# ADC_AUX.net
KiCad netlist of a schematic drawn in Altium Designer
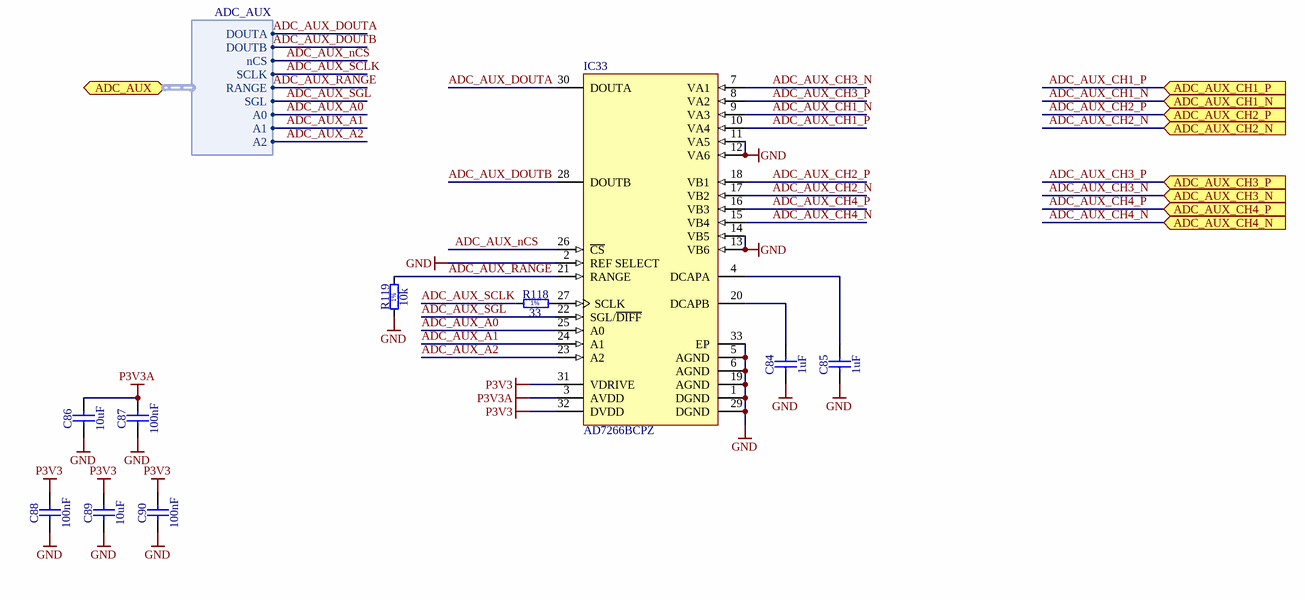
[diagram p0: ADC_AUX.SchDoc]

(export (version "E")
  (design (tool "Eeschema 10.0.6"))
  (components
    (comp (ref "C84")
      (value "1uF")
      (footprint "CAPC1005X55N")
      (description "Non-polarised capacitor")
      (fields
        (field (name "PART NUMBER") "CC0402_1UF_16V_10%_X5R")
        (field (name "VOLTAGE") "16V")
        (field (name "AUTHOR") "CERN DEM JLC")
      )
      (libsource (lib "Capacitors") (part "Capacitor - non polarized"))
    )
    (comp (ref "C85")
      (value "1uF")
      (footprint "CAPC1005X55N")
      (description "Non-polarised capacitor")
      (fields
        (field (name "PART NUMBER") "CC0402_1UF_16V_10%_X5R")
        (field (name "VOLTAGE") "16V")
        (field (name "AUTHOR") "CERN DEM JLC")
      )
      (libsource (lib "Capacitors") (part "Capacitor - non polarized"))
    )
    (comp (ref "C86")
      (value "10uF")
      (footprint "CAPC1608X80N")
      (description "Non-polarised capacitor")
      (fields
        (field (name "PART NUMBER") "CC0603_10UF_10V_10%_X5R")
        (field (name "VOLTAGE") "10V")
        (field (name "AUTHOR") "CERN DEM JLC")
      )
      (libsource (lib "Capacitors") (part "Capacitor - non polarized"))
    )
    (comp (ref "C87")
      (value "100nF")
      (footprint "CAPC1005X55N")
      (description "Non-polarised capacitor")
      (fields
        (field (name "PART NUMBER") "CC0402_100NF_16V_10%_X7R")
        (field (name "VOLTAGE") "16V")
        (field (name "AUTHOR") "CERN DEM JLC")
      )
      (libsource (lib "Capacitors") (part "Capacitor - non polarized"))
    )
    (comp (ref "C88")
      (value "100nF")
      (footprint "CAPC1005X55N")
      (description "Non-polarised capacitor")
      (fields
        (field (name "PART NUMBER") "CC0402_100NF_16V_10%_X7R")
        (field (name "VOLTAGE") "16V")
        (field (name "AUTHOR") "CERN DEM JLC")
      )
      (libsource (lib "Capacitors") (part "Capacitor - non polarized"))
    )
    (comp (ref "C89")
      (value "10uF")
      (footprint "CAPC1608X80N")
      (description "Non-polarised capacitor")
      (fields
        (field (name "PART NUMBER") "CC0603_10UF_10V_10%_X5R")
        (field (name "VOLTAGE") "10V")
        (field (name "AUTHOR") "CERN DEM JLC")
      )
      (libsource (lib "Capacitors") (part "Capacitor - non polarized"))
    )
    (comp (ref "C90")
      (value "100nF")
      (footprint "CAPC1005X55N")
      (description "Non-polarised capacitor")
      (fields
        (field (name "PART NUMBER") "CC0402_100NF_16V_10%_X7R")
        (field (name "VOLTAGE") "16V")
        (field (name "AUTHOR") "CERN DEM JLC")
      )
      (libsource (lib "Capacitors") (part "Capacitor - non polarized"))
    )
    (comp (ref "IC33")
      (value "AD7266BCPZ")
      (footprint "CP-32-2_N")
      (fields (field (name "MANUFACTURER") "Analog Devices") (field (name "GENERIC PART NUMBER") "AD7266"))
      (libsource (lib "Altium Content Vault") (part "ADI-AD7266-CP-32-2"))
    )
    (comp (ref "R118")
      (value "33")
      (footprint "RESC1005X40N")
      (description "Resistor - 1%")
      (fields
        (field (name "PART NUMBER") "R0402_33R_1%_0.0625W_100PPM")
        (field (name "MANUFACTURER") "GENERIC")
        (field (name "AUTHOR") "CERN DEM JLC")
      )
      (libsource (lib "Resistors") (part "Resistor - 1%"))
    )
    (comp (ref "R119")
      (value "10k")
      (footprint "RESC1005X40N")
      (description "Resistor - 1%")
      (fields
        (field (name "PART NUMBER") "R0402_10K_1%_0.0625W_100PPM")
        (field (name "MANUFACTURER") "GENERIC")
        (field (name "AUTHOR") "CERN DEM JLC")
      )
      (libsource (lib "Resistors") (part "Resistor - 1%"))
    )
  )
  (nets
    (net (code "2") (name "/ADC_AUX_A0") (class "Default")
      (node (ref "IC33") (pin "25") (pinfunction "A0_25") (pintype "input"))
    )
    (net (code "3") (name "/ADC_AUX_A1") (class "Default")
      (node (ref "IC33") (pin "24") (pinfunction "A1_24") (pintype "input"))
    )
    (net (code "4") (name "/ADC_AUX_A2") (class "Default")
      (node (ref "IC33") (pin "23") (pinfunction "A2_23") (pintype "input"))
    )
    (net (code "5") (name "/ADC_AUX_CH1_N") (class "Default")
      (node (ref "IC33") (pin "9") (pinfunction "VA3_9") (pintype "input"))
    )
    (net (code "6") (name "/ADC_AUX_CH1_P") (class "Default")
      (node (ref "IC33") (pin "10") (pinfunction "VA4_10") (pintype "input"))
    )
    (net (code "7") (name "/ADC_AUX_CH2_N") (class "Default")
      (node (ref "IC33") (pin "17") (pinfunction "VB2_17") (pintype "input"))
    )
    (net (code "8") (name "/ADC_AUX_CH2_P") (class "Default")
      (node (ref "IC33") (pin "18") (pinfunction "VB1_18") (pintype "input"))
    )
    (net (code "9") (name "/ADC_AUX_CH3_N") (class "Default")
      (node (ref "IC33") (pin "7") (pinfunction "VA1_7") (pintype "input"))
    )
    (net (code "10") (name "/ADC_AUX_CH3_P") (class "Default")
      (node (ref "IC33") (pin "8") (pinfunction "VA2_8") (pintype "input"))
    )
    (net (code "11") (name "/ADC_AUX_CH4_N") (class "Default")
      (node (ref "IC33") (pin "15") (pinfunction "VB4_15") (pintype "input"))
    )
    (net (code "12") (name "/ADC_AUX_CH4_P") (class "Default")
      (node (ref "IC33") (pin "16") (pinfunction "VB3_16") (pintype "input"))
    )
    (net (code "13") (name "/ADC_AUX_DOUTA") (class "Default")
      (node (ref "IC33") (pin "30") (pinfunction "DOUTA_30") (pintype "tri_state"))
    )
    (net (code "14") (name "/ADC_AUX_DOUTB") (class "Default")
      (node (ref "IC33") (pin "28") (pinfunction "DOUTB_28") (pintype "tri_state"))
    )
    (net (code "15") (name "/ADC_AUX_RANGE") (class "Default")
      (node (ref "IC33") (pin "21") (pinfunction "RANGE_21") (pintype "input"))
      (node (ref "R119") (pin "2") (pinfunction "2_2") (pintype "passive"))
    )
    (net (code "16") (name "/ADC_AUX_SCLK") (class "Default")
      (node (ref "R118") (pin "1") (pinfunction "1_1") (pintype "passive"))
    )
    (net (code "17") (name "/ADC_AUX_SGL") (class "Default")
      (node (ref "IC33") (pin "22") (pinfunction "SGL/~{DIFF}_22") (pintype "input"))
    )
    (net (code "18") (name "/ADC_AUX_nCS") (class "Default")
      (node (ref "IC33") (pin "26") (pinfunction "~{CS}_26") (pintype "input"))
    )
    (net (code "20") (name "GND") (class "Default")
      (node (ref "C84") (pin "1") (pinfunction "1_1") (pintype "passive"))
      (node (ref "C85") (pin "1") (pinfunction "1_1") (pintype "passive"))
      (node (ref "C86") (pin "1") (pinfunction "1_1") (pintype "passive"))
      (node (ref "C87") (pin "1") (pinfunction "1_1") (pintype "passive"))
      (node (ref "C88") (pin "1") (pinfunction "1_1") (pintype "passive"))
      (node (ref "C89") (pin "1") (pinfunction "1_1") (pintype "passive"))
      (node (ref "C90") (pin "1") (pinfunction "1_1") (pintype "passive"))
      (node (ref "IC33") (pin "1") (pinfunction "DGND_1") (pintype "power_in"))
      (node (ref "IC33") (pin "11") (pinfunction "VA5_11") (pintype "input"))
      (node (ref "IC33") (pin "12") (pinfunction "VA6_12") (pintype "input"))
      (node (ref "IC33") (pin "13") (pinfunction "VB6_13") (pintype "input"))
      (node (ref "IC33") (pin "14") (pinfunction "VB5_14") (pintype "input"))
      (node (ref "IC33") (pin "19") (pinfunction "AGND_19") (pintype "power_in"))
      (node (ref "IC33") (pin "2") (pinfunction "REF_SELECT_2") (pintype "input"))
      (node (ref "IC33") (pin "29") (pinfunction "DGND_29") (pintype "power_in"))
      (node (ref "IC33") (pin "33") (pinfunction "EP_33") (pintype "power_in"))
      (node (ref "IC33") (pin "5") (pinfunction "AGND_5") (pintype "power_in"))
      (node (ref "IC33") (pin "6") (pinfunction "AGND_6") (pintype "power_in"))
      (node (ref "R119") (pin "1") (pinfunction "1_1") (pintype "passive"))
    )
    (net (code "21") (name "Net-(IC33-DCAPA)") (class "Default")
      (node (ref "C85") (pin "2") (pinfunction "2_2") (pintype "passive"))
      (node (ref "IC33") (pin "4") (pinfunction "DCAPA_4") (pintype "passive"))
    )
    (net (code "22") (name "Net-(IC33-DCAPB)") (class "Default")
      (node (ref "C84") (pin "2") (pinfunction "2_2") (pintype "passive"))
      (node (ref "IC33") (pin "20") (pinfunction "DCAPB_20") (pintype "passive"))
    )
    (net (code "23") (name "Net-(IC33-SCLK)") (class "Default")
      (node (ref "IC33") (pin "27") (pinfunction "SCLK_27") (pintype "input"))
      (node (ref "R118") (pin "2") (pinfunction "2_2") (pintype "passive"))
    )
    (net (code "24") (name "P3V3") (class "Default")
      (node (ref "C88") (pin "2") (pinfunction "2_2") (pintype "passive"))
      (node (ref "C89") (pin "2") (pinfunction "2_2") (pintype "passive"))
      (node (ref "C90") (pin "2") (pinfunction "2_2") (pintype "passive"))
      (node (ref "IC33") (pin "31") (pinfunction "VDRIVE_31") (pintype "power_in"))
      (node (ref "IC33") (pin "32") (pinfunction "DVDD_32") (pintype "power_in"))
    )
    (net (code "25") (name "P3V3A") (class "Default")
      (node (ref "C86") (pin "2") (pinfunction "2_2") (pintype "passive"))
      (node (ref "C87") (pin "2") (pinfunction "2_2") (pintype "passive"))
      (node (ref "IC33") (pin "3") (pinfunction "AVDD_3") (pintype "power_in"))
    )
  )
)
